# vixen1.net
KiCad netlist of a schematic drawn in EAGLE
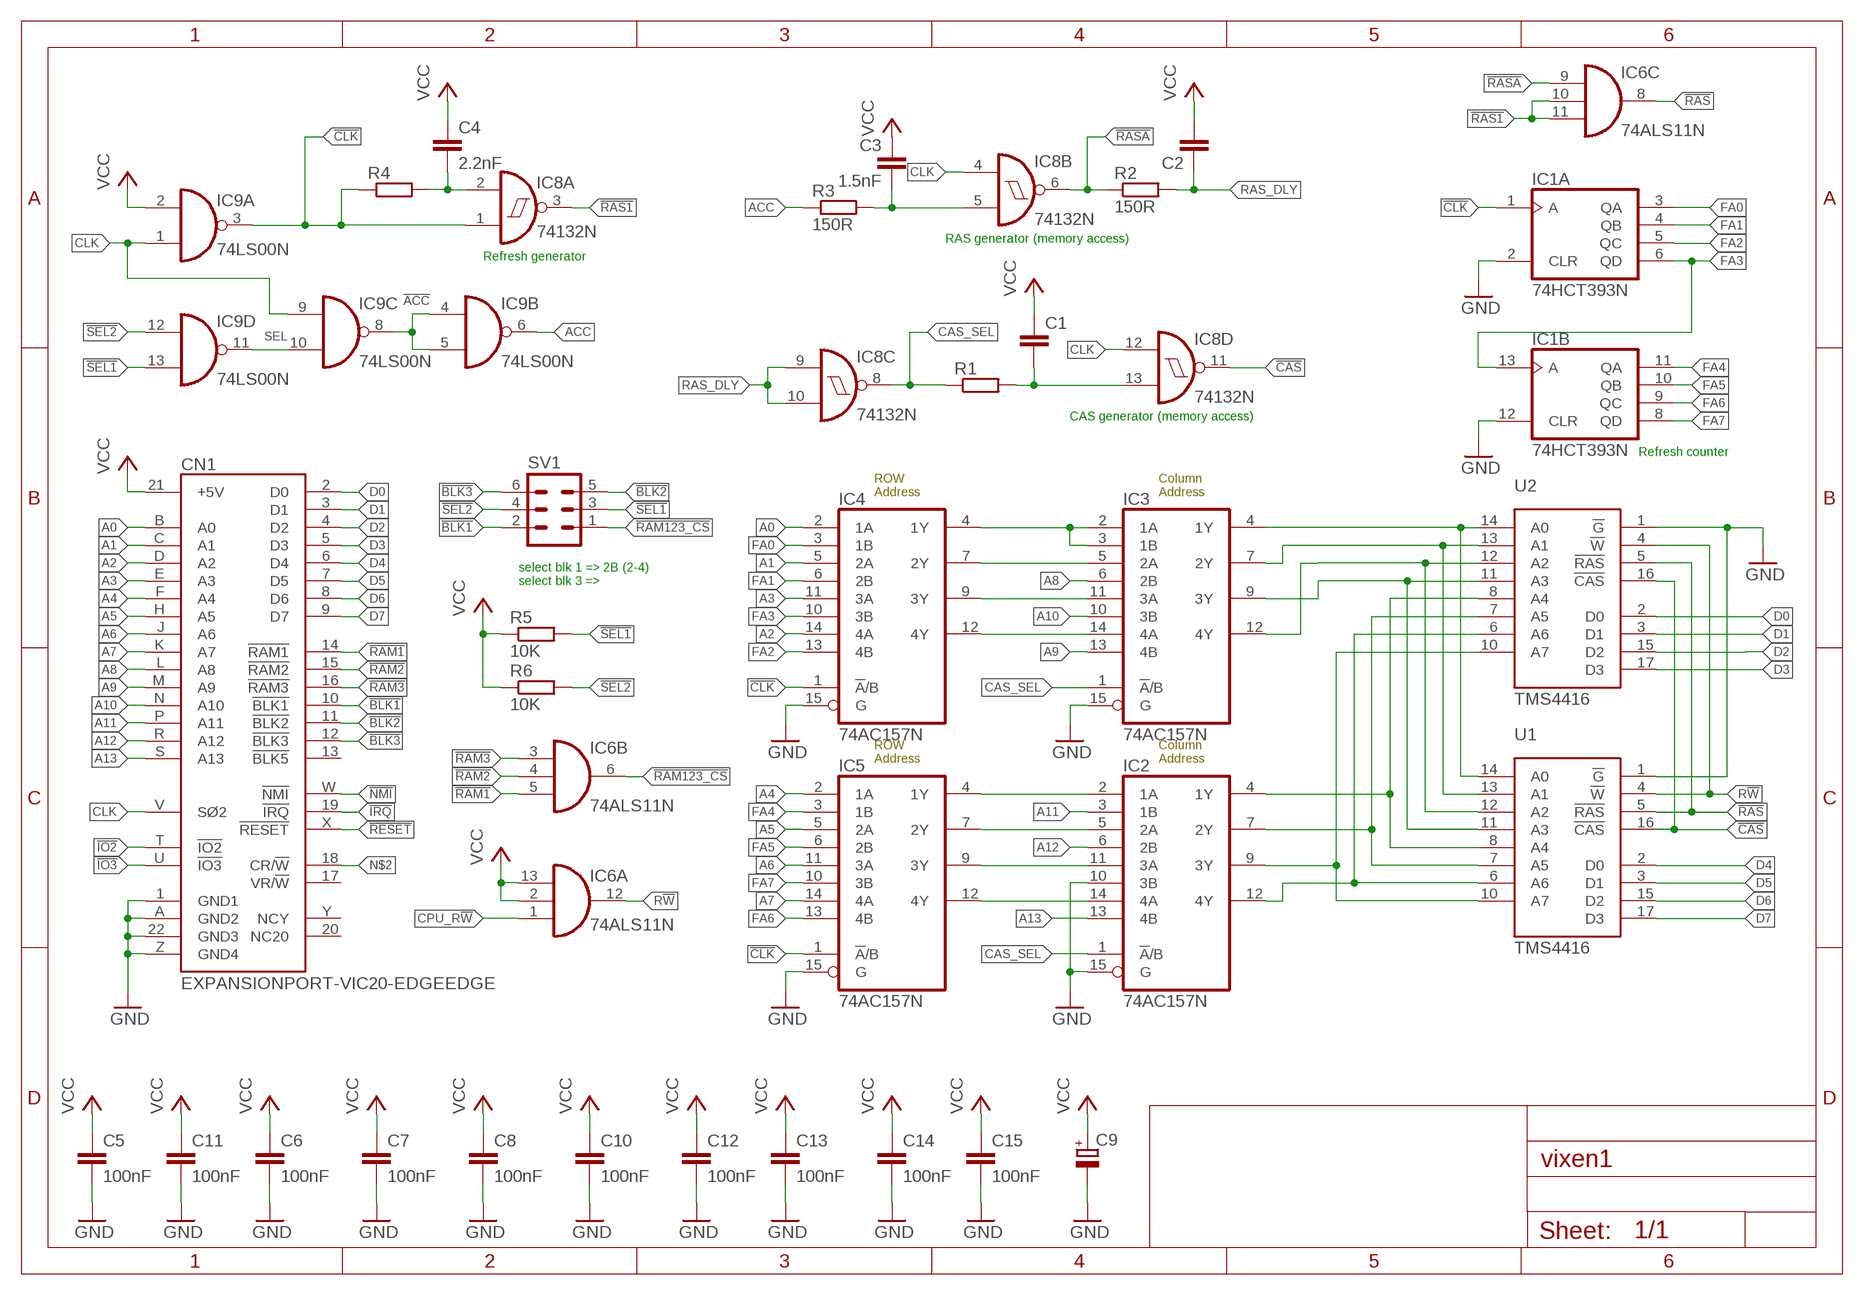
[diagram p0: schematic, sheet 1]

(export (version "E")
  (design (tool "Eeschema 10.0.6"))
  (components
    (comp (ref "C1")
      (value "C-EU025-025X050")
      (footprint "eagle-import:C025-025X050")
      (libsource (lib "eagle-import") (part "C-EU025-025X050"))
    )
    (comp (ref "C2")
      (value "C-EU025-025X050")
      (footprint "eagle-import:C025-025X050")
      (libsource (lib "eagle-import") (part "C-EU025-025X050"))
    )
    (comp (ref "C3")
      (value "1.5nF")
      (footprint "eagle-import:C025-025X050")
      (libsource (lib "eagle-import") (part "C-EU025-025X050"))
    )
    (comp (ref "C4")
      (value "2.2nF")
      (footprint "eagle-import:C025-025X050")
      (libsource (lib "eagle-import") (part "C-EU025-025X050"))
    )
    (comp (ref "C5")
      (value "100nF")
      (footprint "eagle-import:C025-025X050")
      (libsource (lib "eagle-import") (part "C-EU025-025X050"))
    )
    (comp (ref "C6")
      (value "100nF")
      (footprint "eagle-import:C025-025X050")
      (libsource (lib "eagle-import") (part "C-EU025-025X050"))
    )
    (comp (ref "C7")
      (value "100nF")
      (footprint "eagle-import:C025-025X050")
      (libsource (lib "eagle-import") (part "C-EU025-025X050"))
    )
    (comp (ref "C8")
      (value "100nF")
      (footprint "eagle-import:C025-025X050")
      (libsource (lib "eagle-import") (part "C-EU025-025X050"))
    )
    (comp (ref "C9")
      (value "CPOL-EUE15-5AXIAL")
      (footprint "eagle-import:E15-5")
      (libsource (lib "eagle-import") (part "CPOL-EUE15-5AXIAL"))
    )
    (comp (ref "C10")
      (value "100nF")
      (footprint "eagle-import:C025-025X050")
      (libsource (lib "eagle-import") (part "C-EU025-025X050"))
    )
    (comp (ref "C11")
      (value "100nF")
      (footprint "eagle-import:C025-025X050")
      (libsource (lib "eagle-import") (part "C-EU025-025X050"))
    )
    (comp (ref "C12")
      (value "100nF")
      (footprint "eagle-import:C025-025X050")
      (libsource (lib "eagle-import") (part "C-EU025-025X050"))
    )
    (comp (ref "C13")
      (value "100nF")
      (footprint "eagle-import:C025-025X050")
      (libsource (lib "eagle-import") (part "C-EU025-025X050"))
    )
    (comp (ref "C14")
      (value "100nF")
      (footprint "eagle-import:C025-025X050")
      (libsource (lib "eagle-import") (part "C-EU025-025X050"))
    )
    (comp (ref "C15")
      (value "100nF")
      (footprint "eagle-import:C025-025X050")
      (libsource (lib "eagle-import") (part "C-EU025-025X050"))
    )
    (comp (ref "CN1")
      (value "EXPANSIONPORT-VIC20-EDGEEDGE")
      (footprint "eagle-import:UPS44EDGE")
      (libsource (lib "eagle-import") (part "EXPANSIONPORT-VIC20-EDGEEDGE"))
    )
    (comp (ref "IC1")
      (value "74HCT393N")
      (footprint "eagle-import:DIL14")
      (libsource (lib "eagle-import") (part "74393NHCT"))
    )
    (comp (ref "IC2")
      (value "74AC157N")
      (footprint "eagle-import:DIL16")
      (libsource (lib "eagle-import") (part "74157NAC"))
    )
    (comp (ref "IC3")
      (value "74AC157N")
      (footprint "eagle-import:DIL16")
      (libsource (lib "eagle-import") (part "74157NAC"))
    )
    (comp (ref "IC4")
      (value "74AC157N")
      (footprint "eagle-import:DIL16")
      (libsource (lib "eagle-import") (part "74157NAC"))
    )
    (comp (ref "IC5")
      (value "74AC157N")
      (footprint "eagle-import:DIL16")
      (libsource (lib "eagle-import") (part "74157NAC"))
    )
    (comp (ref "IC6")
      (value "74ALS11N")
      (footprint "eagle-import:DIL14")
      (libsource (lib "eagle-import") (part "7411NALS"))
    )
    (comp (ref "IC8")
      (value "74132N")
      (footprint "eagle-import:DIL14")
      (libsource (lib "eagle-import") (part "74132N"))
    )
    (comp (ref "IC9")
      (value "74LS00N")
      (footprint "eagle-import:DIL14")
      (libsource (lib "eagle-import") (part "7400NLS"))
    )
    (comp (ref "R1")
      (value "R-EU_0204/7")
      (footprint "eagle-import:0204_7")
      (libsource (lib "eagle-import") (part "R-EU_0204/7"))
    )
    (comp (ref "R2")
      (value "150R")
      (footprint "eagle-import:0204_7")
      (libsource (lib "eagle-import") (part "R-EU_0204/7"))
    )
    (comp (ref "R3")
      (value "150R")
      (footprint "eagle-import:0204_7")
      (libsource (lib "eagle-import") (part "R-EU_0204/7"))
    )
    (comp (ref "R4")
      (value "R-EU_0204/7")
      (footprint "eagle-import:0204_7")
      (libsource (lib "eagle-import") (part "R-EU_0204/7"))
    )
    (comp (ref "R5")
      (value "10K")
      (footprint "eagle-import:0204_7")
      (libsource (lib "eagle-import") (part "R-EU_0204/7"))
    )
    (comp (ref "R6")
      (value "10K")
      (footprint "eagle-import:0204_7")
      (libsource (lib "eagle-import") (part "R-EU_0204/7"))
    )
    (comp (ref "SV1")
      (value "MA03-2")
      (footprint "eagle-import:MA03-2")
      (libsource (lib "eagle-import") (part "MA03-2"))
    )
    (comp (ref "U1")
      (value "TMS4416")
      (footprint "eagle-import:DIL18")
      (libsource (lib "eagle-import") (part "TMS4416"))
    )
    (comp (ref "U2")
      (value "TMS4416")
      (footprint "eagle-import:DIL18")
      (libsource (lib "eagle-import") (part "TMS4416"))
    )
  )
  (nets
    (net (code "1") (name "/CPU_R~{W}") (class "Default")
      (node (ref "IC6") (pin "1") (pinfunction "I0_1") (pintype "input"))
    )
    (net (code "2") (name "/R~{W}") (class "Default")
      (node (ref "IC6") (pin "12") (pinfunction "O_12") (pintype "output"))
      (node (ref "U1") (pin "4") (pinfunction "~{W}_4") (pintype "bidirectional"))
      (node (ref "U2") (pin "4") (pinfunction "~{W}_4") (pintype "bidirectional"))
    )
    (net (code "3") (name "/SEL") (class "Default")
      (node (ref "IC9") (pin "10") (pinfunction "I1_10") (pintype "input"))
      (node (ref "IC9") (pin "11") (pinfunction "O_11") (pintype "output"))
    )
    (net (code "4") (name "/~{ACC}") (class "Default")
      (node (ref "IC9") (pin "4") (pinfunction "I0_4") (pintype "input"))
      (node (ref "IC9") (pin "5") (pinfunction "I1_5") (pintype "input"))
      (node (ref "IC9") (pin "8") (pinfunction "O_8") (pintype "output"))
    )
    (net (code "5") (name "/~{BLK1}") (class "Default")
      (node (ref "CN1") (pin "10") (pinfunction "~{BLK1}_10") (pintype "output"))
      (node (ref "SV1") (pin "2") (pinfunction "2_2") (pintype "passive"))
    )
    (net (code "6") (name "/~{BLK2}") (class "Default")
      (node (ref "CN1") (pin "11") (pinfunction "~{BLK2}_11") (pintype "output"))
      (node (ref "SV1") (pin "5") (pinfunction "5_5") (pintype "passive"))
    )
    (net (code "7") (name "/~{BLK3}") (class "Default")
      (node (ref "CN1") (pin "12") (pinfunction "~{BLK3}_12") (pintype "output"))
      (node (ref "SV1") (pin "6") (pinfunction "6_6") (pintype "passive"))
    )
    (net (code "8") (name "/~{CAS}") (class "Default")
      (node (ref "IC8") (pin "11") (pinfunction "O_11") (pintype "output"))
      (node (ref "U1") (pin "16") (pinfunction "~{CAS}_16") (pintype "bidirectional"))
      (node (ref "U2") (pin "16") (pinfunction "~{CAS}_16") (pintype "bidirectional"))
    )
    (net (code "9") (name "/~{CLK}") (class "Default")
      (node (ref "IC1") (pin "1") (pinfunction "A_1") (pintype "input"))
      (node (ref "IC4") (pin "1") (pinfunction "~{A}/B_1") (pintype "input"))
      (node (ref "IC5") (pin "1") (pinfunction "~{A}/B_1") (pintype "input"))
      (node (ref "IC8") (pin "1") (pinfunction "I0_1") (pintype "input"))
      (node (ref "IC9") (pin "3") (pinfunction "O_3") (pintype "output"))
      (node (ref "R4") (pin "1") (pinfunction "1_1") (pintype "passive"))
    )
    (net (code "10") (name "/~{IO2}") (class "Default")
      (node (ref "CN1") (pin "T") (pinfunction "~{IO2}_T") (pintype "output"))
    )
    (net (code "11") (name "/~{IO3}") (class "Default")
      (node (ref "CN1") (pin "U") (pinfunction "~{IO3}_U") (pintype "output"))
    )
    (net (code "12") (name "/~{IRQ}") (class "Default")
      (node (ref "CN1") (pin "19") (pinfunction "~{IRQ}_19") (pintype "bidirectional"))
    )
    (net (code "13") (name "/~{NMI}") (class "Default")
      (node (ref "CN1") (pin "W") (pinfunction "~{NMI}_W") (pintype "bidirectional"))
    )
    (net (code "14") (name "/~{RAM1}") (class "Default")
      (node (ref "CN1") (pin "14") (pinfunction "~{RAM1}_14") (pintype "output"))
      (node (ref "IC6") (pin "5") (pinfunction "I2_5") (pintype "input"))
    )
    (net (code "15") (name "/~{RAM2}") (class "Default")
      (node (ref "CN1") (pin "15") (pinfunction "~{RAM2}_15") (pintype "output"))
      (node (ref "IC6") (pin "4") (pinfunction "I1_4") (pintype "input"))
    )
    (net (code "16") (name "/~{RAM3}") (class "Default")
      (node (ref "CN1") (pin "16") (pinfunction "~{RAM3}_16") (pintype "output"))
      (node (ref "IC6") (pin "3") (pinfunction "I0_3") (pintype "input"))
    )
    (net (code "17") (name "/~{RAM123_CS}") (class "Default")
      (node (ref "IC6") (pin "6") (pinfunction "O_6") (pintype "output"))
      (node (ref "SV1") (pin "1") (pinfunction "1_1") (pintype "passive"))
    )
    (net (code "18") (name "/~{RAS1}") (class "Default")
      (node (ref "IC6") (pin "10") (pinfunction "I1_10") (pintype "input"))
      (node (ref "IC6") (pin "11") (pinfunction "I2_11") (pintype "input"))
      (node (ref "IC8") (pin "3") (pinfunction "O_3") (pintype "output"))
    )
    (net (code "19") (name "/~{RASA}") (class "Default")
      (node (ref "IC6") (pin "9") (pinfunction "I0_9") (pintype "input"))
      (node (ref "IC8") (pin "6") (pinfunction "O_6") (pintype "output"))
      (node (ref "R2") (pin "1") (pinfunction "1_1") (pintype "passive"))
    )
    (net (code "20") (name "/~{RAS}") (class "Default")
      (node (ref "IC6") (pin "8") (pinfunction "O_8") (pintype "output"))
      (node (ref "U1") (pin "5") (pinfunction "~{RAS}_5") (pintype "bidirectional"))
      (node (ref "U2") (pin "5") (pinfunction "~{RAS}_5") (pintype "bidirectional"))
    )
    (net (code "21") (name "/~{RESET}") (class "Default")
      (node (ref "CN1") (pin "X") (pinfunction "~{RESET}_X") (pintype "bidirectional"))
    )
    (net (code "22") (name "/~{SEL1}") (class "Default")
      (node (ref "IC9") (pin "13") (pinfunction "I1_13") (pintype "input"))
      (node (ref "R5") (pin "2") (pinfunction "2_2") (pintype "passive"))
      (node (ref "SV1") (pin "3") (pinfunction "3_3") (pintype "passive"))
    )
    (net (code "23") (name "/~{SEL2}") (class "Default")
      (node (ref "IC9") (pin "12") (pinfunction "I0_12") (pintype "input"))
      (node (ref "R6") (pin "2") (pinfunction "2_2") (pintype "passive"))
      (node (ref "SV1") (pin "4") (pinfunction "4_4") (pintype "passive"))
    )
    (net (code "24") (name "A0") (class "Default")
      (node (ref "CN1") (pin "B") (pinfunction "A0_B") (pintype "output"))
      (node (ref "IC4") (pin "2") (pinfunction "1A_2") (pintype "input"))
    )
    (net (code "25") (name "A1") (class "Default")
      (node (ref "CN1") (pin "C") (pinfunction "A1_C") (pintype "output"))
      (node (ref "IC4") (pin "5") (pinfunction "2A_5") (pintype "input"))
    )
    (net (code "26") (name "A2") (class "Default")
      (node (ref "CN1") (pin "D") (pinfunction "A2_D") (pintype "output"))
      (node (ref "IC4") (pin "14") (pinfunction "4A_14") (pintype "input"))
    )
    (net (code "27") (name "A3") (class "Default")
      (node (ref "CN1") (pin "E") (pinfunction "A3_E") (pintype "output"))
      (node (ref "IC4") (pin "11") (pinfunction "3A_11") (pintype "input"))
    )
    (net (code "28") (name "A4") (class "Default")
      (node (ref "CN1") (pin "F") (pinfunction "A4_F") (pintype "output"))
      (node (ref "IC5") (pin "2") (pinfunction "1A_2") (pintype "input"))
    )
    (net (code "29") (name "A5") (class "Default")
      (node (ref "CN1") (pin "H") (pinfunction "A5_H") (pintype "output"))
      (node (ref "IC5") (pin "5") (pinfunction "2A_5") (pintype "input"))
    )
    (net (code "30") (name "A6") (class "Default")
      (node (ref "CN1") (pin "J") (pinfunction "A6_J") (pintype "output"))
      (node (ref "IC5") (pin "11") (pinfunction "3A_11") (pintype "input"))
    )
    (net (code "31") (name "A7") (class "Default")
      (node (ref "CN1") (pin "K") (pinfunction "A7_K") (pintype "output"))
      (node (ref "IC5") (pin "14") (pinfunction "4A_14") (pintype "input"))
    )
    (net (code "32") (name "A8") (class "Default")
      (node (ref "CN1") (pin "L") (pinfunction "A8_L") (pintype "output"))
      (node (ref "IC3") (pin "6") (pinfunction "2B_6") (pintype "input"))
    )
    (net (code "33") (name "A9") (class "Default")
      (node (ref "CN1") (pin "M") (pinfunction "A9_M") (pintype "output"))
      (node (ref "IC3") (pin "13") (pinfunction "4B_13") (pintype "input"))
    )
    (net (code "34") (name "A10") (class "Default")
      (node (ref "CN1") (pin "N") (pinfunction "A10_N") (pintype "output"))
      (node (ref "IC3") (pin "10") (pinfunction "3B_10") (pintype "input"))
    )
    (net (code "35") (name "A11") (class "Default")
      (node (ref "CN1") (pin "P") (pinfunction "A11_P") (pintype "output"))
      (node (ref "IC2") (pin "3") (pinfunction "1B_3") (pintype "input"))
    )
    (net (code "36") (name "A12") (class "Default")
      (node (ref "CN1") (pin "R") (pinfunction "A12_R") (pintype "output"))
      (node (ref "IC2") (pin "6") (pinfunction "2B_6") (pintype "input"))
    )
    (net (code "37") (name "A13") (class "Default")
      (node (ref "CN1") (pin "S") (pinfunction "A13_S") (pintype "output"))
      (node (ref "IC2") (pin "13") (pinfunction "4B_13") (pintype "input"))
    )
    (net (code "38") (name "ACC") (class "Default")
      (node (ref "IC9") (pin "6") (pinfunction "O_6") (pintype "output"))
      (node (ref "R3") (pin "1") (pinfunction "1_1") (pintype "passive"))
    )
    (net (code "39") (name "CAS_SEL") (class "Default")
      (node (ref "IC2") (pin "1") (pinfunction "~{A}/B_1") (pintype "input"))
      (node (ref "IC3") (pin "1") (pinfunction "~{A}/B_1") (pintype "input"))
      (node (ref "IC8") (pin "8") (pinfunction "O_8") (pintype "output"))
      (node (ref "R1") (pin "1") (pinfunction "1_1") (pintype "passive"))
    )
    (net (code "40") (name "CLK") (class "Default")
      (node (ref "CN1") (pin "V") (pinfunction "SØ2_V") (pintype "output"))
      (node (ref "IC8") (pin "12") (pinfunction "I0_12") (pintype "input"))
      (node (ref "IC8") (pin "4") (pinfunction "I0_4") (pintype "input"))
      (node (ref "IC9") (pin "1") (pinfunction "I0_1") (pintype "input"))
      (node (ref "IC9") (pin "9") (pinfunction "I0_9") (pintype "input"))
    )
    (net (code "41") (name "D0") (class "Default")
      (node (ref "CN1") (pin "2") (pinfunction "D0_2") (pintype "bidirectional"))
      (node (ref "U2") (pin "2") (pinfunction "D0_2") (pintype "bidirectional"))
    )
    (net (code "42") (name "D1") (class "Default")
      (node (ref "CN1") (pin "3") (pinfunction "D1_3") (pintype "bidirectional"))
      (node (ref "U2") (pin "3") (pinfunction "D1_3") (pintype "bidirectional"))
    )
    (net (code "43") (name "D2") (class "Default")
      (node (ref "CN1") (pin "4") (pinfunction "D2_4") (pintype "bidirectional"))
      (node (ref "U2") (pin "15") (pinfunction "D2_15") (pintype "bidirectional"))
    )
    (net (code "44") (name "D3") (class "Default")
      (node (ref "CN1") (pin "5") (pinfunction "D3_5") (pintype "bidirectional"))
      (node (ref "U2") (pin "17") (pinfunction "D3_17") (pintype "bidirectional"))
    )
    (net (code "45") (name "D4") (class "Default")
      (node (ref "CN1") (pin "6") (pinfunction "D4_6") (pintype "bidirectional"))
      (node (ref "U1") (pin "2") (pinfunction "D0_2") (pintype "bidirectional"))
    )
    (net (code "46") (name "D5") (class "Default")
      (node (ref "CN1") (pin "7") (pinfunction "D5_7") (pintype "bidirectional"))
      (node (ref "U1") (pin "3") (pinfunction "D1_3") (pintype "bidirectional"))
    )
    (net (code "47") (name "D6") (class "Default")
      (node (ref "CN1") (pin "8") (pinfunction "D6_8") (pintype "bidirectional"))
      (node (ref "U1") (pin "15") (pinfunction "D2_15") (pintype "bidirectional"))
    )
    (net (code "48") (name "D7") (class "Default")
      (node (ref "CN1") (pin "9") (pinfunction "D7_9") (pintype "bidirectional"))
      (node (ref "U1") (pin "17") (pinfunction "D3_17") (pintype "bidirectional"))
    )
    (net (code "49") (name "FA0") (class "Default")
      (node (ref "IC1") (pin "3") (pinfunction "QA_3") (pintype "output"))
      (node (ref "IC4") (pin "3") (pinfunction "1B_3") (pintype "input"))
    )
    (net (code "50") (name "FA1") (class "Default")
      (node (ref "IC1") (pin "4") (pinfunction "QB_4") (pintype "output"))
      (node (ref "IC4") (pin "6") (pinfunction "2B_6") (pintype "input"))
    )
    (net (code "51") (name "FA2") (class "Default")
      (node (ref "IC1") (pin "5") (pinfunction "QC_5") (pintype "output"))
      (node (ref "IC4") (pin "13") (pinfunction "4B_13") (pintype "input"))
    )
    (net (code "52") (name "FA3") (class "Default")
      (node (ref "IC1") (pin "13") (pinfunction "A_13") (pintype "input"))
      (node (ref "IC1") (pin "6") (pinfunction "QD_6") (pintype "output"))
      (node (ref "IC4") (pin "10") (pinfunction "3B_10") (pintype "input"))
    )
    (net (code "53") (name "FA4") (class "Default")
      (node (ref "IC1") (pin "11") (pinfunction "QA_11") (pintype "output"))
      (node (ref "IC5") (pin "3") (pinfunction "1B_3") (pintype "input"))
    )
    (net (code "54") (name "FA5") (class "Default")
      (node (ref "IC1") (pin "10") (pinfunction "QB_10") (pintype "output"))
      (node (ref "IC5") (pin "6") (pinfunction "2B_6") (pintype "input"))
    )
    (net (code "55") (name "FA6") (class "Default")
      (node (ref "IC1") (pin "9") (pinfunction "QC_9") (pintype "output"))
      (node (ref "IC5") (pin "13") (pinfunction "4B_13") (pintype "input"))
    )
    (net (code "56") (name "FA7") (class "Default")
      (node (ref "IC1") (pin "8") (pinfunction "QD_8") (pintype "output"))
      (node (ref "IC5") (pin "10") (pinfunction "3B_10") (pintype "input"))
    )
    (net (code "57") (name "GND") (class "Default")
      (node (ref "C10") (pin "2") (pinfunction "2_2") (pintype "passive"))
      (node (ref "C11") (pin "2") (pinfunction "2_2") (pintype "passive"))
      (node (ref "C12") (pin "2") (pinfunction "2_2") (pintype "passive"))
      (node (ref "C13") (pin "2") (pinfunction "2_2") (pintype "passive"))
      (node (ref "C14") (pin "2") (pinfunction "2_2") (pintype "passive"))
      (node (ref "C15") (pin "2") (pinfunction "2_2") (pintype "passive"))
      (node (ref "C5") (pin "2") (pinfunction "2_2") (pintype "passive"))
      (node (ref "C6") (pin "2") (pinfunction "2_2") (pintype "passive"))
      (node (ref "C7") (pin "2") (pinfunction "2_2") (pintype "passive"))
      (node (ref "C8") (pin "2") (pinfunction "2_2") (pintype "passive"))
      (node (ref "C9") (pin "-") (pinfunction "-_-") (pintype "passive"))
      (node (ref "CN1") (pin "1") (pinfunction "GND1_1") (pintype "passive"))
      (node (ref "CN1") (pin "22") (pinfunction "GND3_22") (pintype "passive"))
      (node (ref "CN1") (pin "A") (pinfunction "GND2_A") (pintype "passive"))
      (node (ref "CN1") (pin "Z") (pinfunction "GND4_Z") (pintype "passive"))
      (node (ref "IC1") (pin "12") (pinfunction "CLR_12") (pintype "input"))
      (node (ref "IC1") (pin "2") (pinfunction "CLR_2") (pintype "input"))
      (node (ref "IC2") (pin "10") (pinfunction "3B_10") (pintype "input"))
      (node (ref "IC2") (pin "15") (pinfunction "G_15") (pintype "input"))
      (node (ref "IC3") (pin "15") (pinfunction "G_15") (pintype "input"))
      (node (ref "IC4") (pin "15") (pinfunction "G_15") (pintype "input"))
      (node (ref "IC5") (pin "15") (pinfunction "G_15") (pintype "input"))
      (node (ref "U1") (pin "1") (pinfunction "~{G}_1") (pintype "bidirectional"))
      (node (ref "U2") (pin "1") (pinfunction "~{G}_1") (pintype "bidirectional"))
    )
    (net (code "58") (name "N$2") (class "Default")
      (node (ref "CN1") (pin "18") (pinfunction "CR/~{W}_18") (pintype "output"))
    )
    (net (code "59") (name "Net-(IC2A-1A)") (class "Default")
      (node (ref "IC2") (pin "2") (pinfunction "1A_2") (pintype "input"))
      (node (ref "IC5") (pin "4") (pinfunction "1Y_4") (pintype "output"))
    )
    (net (code "60") (name "Net-(IC2A-1Y)") (class "Default")
      (node (ref "IC2") (pin "4") (pinfunction "1Y_4") (pintype "output"))
      (node (ref "U1") (pin "8") (pinfunction "A4_8") (pintype "input"))
      (node (ref "U2") (pin "8") (pinfunction "A4_8") (pintype "input"))
    )
    (net (code "61") (name "Net-(IC2A-2A)") (class "Default")
      (node (ref "IC2") (pin "5") (pinfunction "2A_5") (pintype "input"))
      (node (ref "IC5") (pin "7") (pinfunction "2Y_7") (pintype "output"))
    )
    (net (code "62") (name "Net-(IC2A-2Y)") (class "Default")
      (node (ref "IC2") (pin "7") (pinfunction "2Y_7") (pintype "output"))
      (node (ref "U1") (pin "7") (pinfunction "A5_7") (pintype "input"))
      (node (ref "U2") (pin "7") (pinfunction "A5_7") (pintype "input"))
    )
    (net (code "63") (name "Net-(IC2A-3A)") (class "Default")
      (node (ref "IC2") (pin "11") (pinfunction "3A_11") (pintype "input"))
      (node (ref "IC5") (pin "9") (pinfunction "3Y_9") (pintype "output"))
    )
    (net (code "64") (name "Net-(IC2A-3Y)") (class "Default")
      (node (ref "IC2") (pin "9") (pinfunction "3Y_9") (pintype "output"))
      (node (ref "U1") (pin "10") (pinfunction "A7_10") (pintype "input"))
      (node (ref "U2") (pin "10") (pinfunction "A7_10") (pintype "input"))
    )
    (net (code "65") (name "Net-(IC2A-4A)") (class "Default")
      (node (ref "IC2") (pin "14") (pinfunction "4A_14") (pintype "input"))
      (node (ref "IC5") (pin "12") (pinfunction "4Y_12") (pintype "output"))
    )
    (net (code "66") (name "Net-(IC2A-4Y)") (class "Default")
      (node (ref "IC2") (pin "12") (pinfunction "4Y_12") (pintype "output"))
      (node (ref "U1") (pin "6") (pinfunction "A6_6") (pintype "input"))
      (node (ref "U2") (pin "6") (pinfunction "A6_6") (pintype "input"))
    )
    (net (code "67") (name "Net-(IC3A-1A)") (class "Default")
      (node (ref "IC3") (pin "2") (pinfunction "1A_2") (pintype "input"))
      (node (ref "IC3") (pin "3") (pinfunction "1B_3") (pintype "input"))
      (node (ref "IC4") (pin "4") (pinfunction "1Y_4") (pintype "output"))
    )
    (net (code "68") (name "Net-(IC3A-1Y)") (class "Default")
      (node (ref "IC3") (pin "4") (pinfunction "1Y_4") (pintype "output"))
      (node (ref "U1") (pin "14") (pinfunction "A0_14") (pintype "input"))
      (node (ref "U2") (pin "14") (pinfunction "A0_14") (pintype "input"))
    )
    (net (code "69") (name "Net-(IC3A-2A)") (class "Default")
      (node (ref "IC3") (pin "5") (pinfunction "2A_5") (pintype "input"))
      (node (ref "IC4") (pin "7") (pinfunction "2Y_7") (pintype "output"))
    )
    (net (code "70") (name "Net-(IC3A-2Y)") (class "Default")
      (node (ref "IC3") (pin "7") (pinfunction "2Y_7") (pintype "output"))
      (node (ref "U1") (pin "13") (pinfunction "A1_13") (pintype "input"))
      (node (ref "U2") (pin "13") (pinfunction "A1_13") (pintype "input"))
    )
    (net (code "71") (name "Net-(IC3A-3A)") (class "Default")
      (node (ref "IC3") (pin "11") (pinfunction "3A_11") (pintype "input"))
      (node (ref "IC4") (pin "9") (pinfunction "3Y_9") (pintype "output"))
    )
    (net (code "72") (name "Net-(IC3A-3Y)") (class "Default")
      (node (ref "IC3") (pin "9") (pinfunction "3Y_9") (pintype "output"))
      (node (ref "U1") (pin "11") (pinfunction "A3_11") (pintype "input"))
      (node (ref "U2") (pin "11") (pinfunction "A3_11") (pintype "input"))
    )
    (net (code "73") (name "Net-(IC3A-4A)") (class "Default")
      (node (ref "IC3") (pin "14") (pinfunction "4A_14") (pintype "input"))
      (node (ref "IC4") (pin "12") (pinfunction "4Y_12") (pintype "output"))
    )
    (net (code "74") (name "Net-(IC3A-4Y)") (class "Default")
      (node (ref "IC3") (pin "12") (pinfunction "4Y_12") (pintype "output"))
      (node (ref "U1") (pin "12") (pinfunction "A2_12") (pintype "input"))
      (node (ref "U2") (pin "12") (pinfunction "A2_12") (pintype "input"))
    )
    (net (code "75") (name "Net-(IC8A-I1)") (class "Default")
      (node (ref "C4") (pin "2") (pinfunction "2_2") (pintype "passive"))
      (node (ref "IC8") (pin "2") (pinfunction "I1_2") (pintype "input"))
      (node (ref "R4") (pin "2") (pinfunction "2_2") (pintype "passive"))
    )
    (net (code "76") (name "Net-(IC8B-I1)") (class "Default")
      (node (ref "C3") (pin "2") (pinfunction "2_2") (pintype "passive"))
      (node (ref "IC8") (pin "5") (pinfunction "I1_5") (pintype "input"))
      (node (ref "R3") (pin "2") (pinfunction "2_2") (pintype "passive"))
    )
    (net (code "77") (name "Net-(IC8D-I1)") (class "Default")
      (node (ref "C1") (pin "2") (pinfunction "2_2") (pintype "passive"))
      (node (ref "IC8") (pin "13") (pinfunction "I1_13") (pintype "input"))
      (node (ref "R1") (pin "2") (pinfunction "2_2") (pintype "passive"))
    )
    (net (code "78") (name "RAS_DLY") (class "Default")
      (node (ref "C2") (pin "1") (pinfunction "1_1") (pintype "passive"))
      (node (ref "IC8") (pin "10") (pinfunction "I1_10") (pintype "input"))
      (node (ref "IC8") (pin "9") (pinfunction "I0_9") (pintype "input"))
      (node (ref "R2") (pin "2") (pinfunction "2_2") (pintype "passive"))
    )
    (net (code "79") (name "VCC") (class "Default")
      (node (ref "C1") (pin "1") (pinfunction "1_1") (pintype "passive"))
      (node (ref "C10") (pin "1") (pinfunction "1_1") (pintype "passive"))
      (node (ref "C11") (pin "1") (pinfunction "1_1") (pintype "passive"))
      (node (ref "C12") (pin "1") (pinfunction "1_1") (pintype "passive"))
      (node (ref "C13") (pin "1") (pinfunction "1_1") (pintype "passive"))
      (node (ref "C14") (pin "1") (pinfunction "1_1") (pintype "passive"))
      (node (ref "C15") (pin "1") (pinfunction "1_1") (pintype "passive"))
      (node (ref "C2") (pin "2") (pinfunction "2_2") (pintype "passive"))
      (node (ref "C3") (pin "1") (pinfunction "1_1") (pintype "passive"))
      (node (ref "C4") (pin "1") (pinfunction "1_1") (pintype "passive"))
      (node (ref "C5") (pin "1") (pinfunction "1_1") (pintype "passive"))
      (node (ref "C6") (pin "1") (pinfunction "1_1") (pintype "passive"))
      (node (ref "C7") (pin "1") (pinfunction "1_1") (pintype "passive"))
      (node (ref "C8") (pin "1") (pinfunction "1_1") (pintype "passive"))
      (node (ref "C9") (pin "+") (pinfunction "+_+") (pintype "passive"))
      (node (ref "CN1") (pin "21") (pinfunction "+5V_21") (pintype "power_in"))
      (node (ref "IC6") (pin "13") (pinfunction "I2_13") (pintype "input"))
      (node (ref "IC6") (pin "2") (pinfunction "I1_2") (pintype "input"))
      (node (ref "IC9") (pin "2") (pinfunction "I1_2") (pintype "input"))
      (node (ref "R5") (pin "1") (pinfunction "1_1") (pintype "passive"))
      (node (ref "R6") (pin "1") (pinfunction "1_1") (pintype "passive"))
    )
    (net (code "80") (name "unconnected-(CN1-NC20-Pad20)") (class "Default")
      (node (ref "CN1") (pin "20") (pinfunction "NC20_20") (pintype "passive"))
    )
    (net (code "81") (name "unconnected-(CN1-NCY-PadY)") (class "Default")
      (node (ref "CN1") (pin "Y") (pinfunction "NCY_Y") (pintype "passive"))
    )
    (net (code "82") (name "unconnected-(CN1-VR{slash}~{W}-Pad17)") (class "Default")
      (node (ref "CN1") (pin "17") (pinfunction "VR/~{W}_17") (pintype "output"))
    )
    (net (code "83") (name "unconnected-(CN1-~{BLK5}-Pad13)") (class "Default")
      (node (ref "CN1") (pin "13") (pinfunction "~{BLK5}_13") (pintype "output"))
    )
  )
)
